# SWD-IR-V01-001.net
KiCad netlist of a schematic drawn in EAGLE
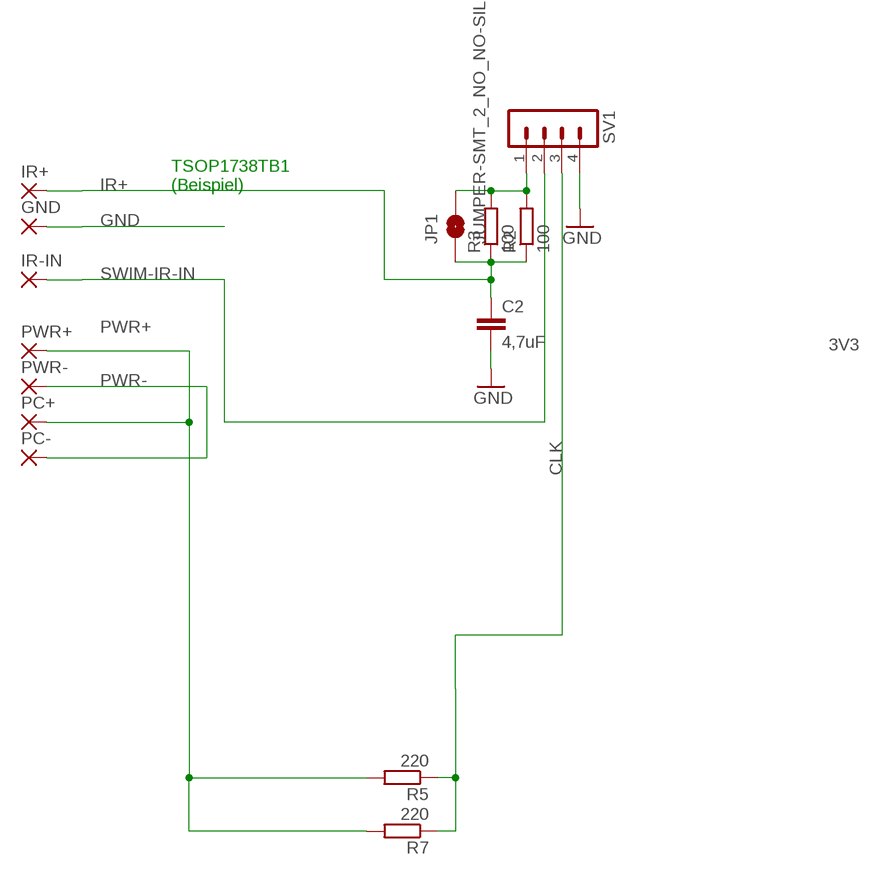
[diagram p0: schematic, sheet 1]

(export (version "E")
  (design (tool "Eeschema 10.0.6"))
  (components
    (comp (ref "C2")
      (value "4,7uF")
      (footprint "eagle-import:C1206K")
      (libsource (lib "eagle-import") (part "C-EUC1206K"))
    )
    (comp (ref "GND")
      (value "SMD2")
      (footprint "eagle-import:SMD1,27-2,54")
      (libsource (lib "eagle-import") (part "SMD2"))
    )
    (comp (ref "IR+")
      (value "SMD2")
      (footprint "eagle-import:SMD1,27-2,54")
      (libsource (lib "eagle-import") (part "SMD2"))
    )
    (comp (ref "IR-IN")
      (value "SMD2")
      (footprint "eagle-import:SMD1,27-2,54")
      (libsource (lib "eagle-import") (part "SMD2"))
    )
    (comp (ref "JP1")
      (value "JUMPER-SMT_2_NO_NO-SILK")
      (footprint "eagle-import:SMT-JUMPER_2_NO_NO-SILK")
      (libsource (lib "eagle-import") (part "JUMPER-SMT_2_NO_NO-SILK"))
    )
    (comp (ref "PC+")
      (value "SMD2")
      (footprint "eagle-import:SMD1,27-2,54")
      (libsource (lib "eagle-import") (part "SMD2"))
    )
    (comp (ref "PC-")
      (value "SMD2")
      (footprint "eagle-import:SMD1,27-2,54")
      (libsource (lib "eagle-import") (part "SMD2"))
    )
    (comp (ref "PWR+")
      (value "SMD2")
      (footprint "eagle-import:SMD1,27-2,54")
      (libsource (lib "eagle-import") (part "SMD2"))
    )
    (comp (ref "PWR-")
      (value "SMD2")
      (footprint "eagle-import:SMD1,27-2,54")
      (libsource (lib "eagle-import") (part "SMD2"))
    )
    (comp (ref "R2")
      (value "100")
      (footprint "eagle-import:0204_7")
      (libsource (lib "eagle-import") (part "R-EU_0204/7"))
    )
    (comp (ref "R3")
      (value "100")
      (footprint "eagle-import:R0805W")
      (libsource (lib "eagle-import") (part "R-EU_R0805W"))
    )
    (comp (ref "R5")
      (value "220")
      (footprint "eagle-import:0204_7")
      (libsource (lib "eagle-import") (part "R-EU_0204/7"))
    )
    (comp (ref "R7")
      (value "220")
      (footprint "eagle-import:R0805W")
      (libsource (lib "eagle-import") (part "R-EU_R0805W"))
    )
    (comp (ref "SV1")
      (value "MA04-1")
      (footprint "eagle-import:MA04-1")
      (libsource (lib "eagle-import") (part "MA04-1"))
    )
  )
  (nets
    (net (code "1") (name "/3V3") (class "Default")
      (node (ref "JP1") (pin "2") (pinfunction "2_2") (pintype "passive"))
      (node (ref "R2") (pin "2") (pinfunction "2_2") (pintype "passive"))
      (node (ref "R3") (pin "2") (pinfunction "2_2") (pintype "passive"))
      (node (ref "SV1") (pin "1") (pinfunction "1_1") (pintype "passive"))
    )
    (net (code "2") (name "/CLK") (class "Default")
      (node (ref "R5") (pin "1") (pinfunction "1_1") (pintype "passive"))
      (node (ref "R7") (pin "1") (pinfunction "1_1") (pintype "passive"))
      (node (ref "SV1") (pin "3") (pinfunction "3_3") (pintype "passive"))
    )
    (net (code "3") (name "/IR+") (class "Default")
      (node (ref "C2") (pin "1") (pinfunction "1_1") (pintype "passive"))
      (node (ref "IR+") (pin "1") (pinfunction "P_1") (pintype "passive"))
      (node (ref "JP1") (pin "1") (pinfunction "1_1") (pintype "passive"))
      (node (ref "R2") (pin "1") (pinfunction "1_1") (pintype "passive"))
      (node (ref "R3") (pin "1") (pinfunction "1_1") (pintype "passive"))
    )
    (net (code "4") (name "/PWR+") (class "Default")
      (node (ref "PC+") (pin "1") (pinfunction "P_1") (pintype "passive"))
      (node (ref "PWR+") (pin "1") (pinfunction "P_1") (pintype "passive"))
      (node (ref "R5") (pin "2") (pinfunction "2_2") (pintype "passive"))
      (node (ref "R7") (pin "2") (pinfunction "2_2") (pintype "passive"))
    )
    (net (code "5") (name "/PWR-") (class "Default")
      (node (ref "PC-") (pin "1") (pinfunction "P_1") (pintype "passive"))
      (node (ref "PWR-") (pin "1") (pinfunction "P_1") (pintype "passive"))
    )
    (net (code "6") (name "/SWIM-IR-IN") (class "Default")
      (node (ref "IR-IN") (pin "1") (pinfunction "P_1") (pintype "passive"))
      (node (ref "SV1") (pin "2") (pinfunction "2_2") (pintype "passive"))
    )
    (net (code "7") (name "GND") (class "Default")
      (node (ref "C2") (pin "2") (pinfunction "2_2") (pintype "passive"))
      (node (ref "GND") (pin "1") (pinfunction "P_1") (pintype "passive"))
      (node (ref "SV1") (pin "4") (pinfunction "4_4") (pintype "passive"))
    )
  )
)
